# String_Shooter.net
KiCad netlist of a schematic drawn in EAGLE
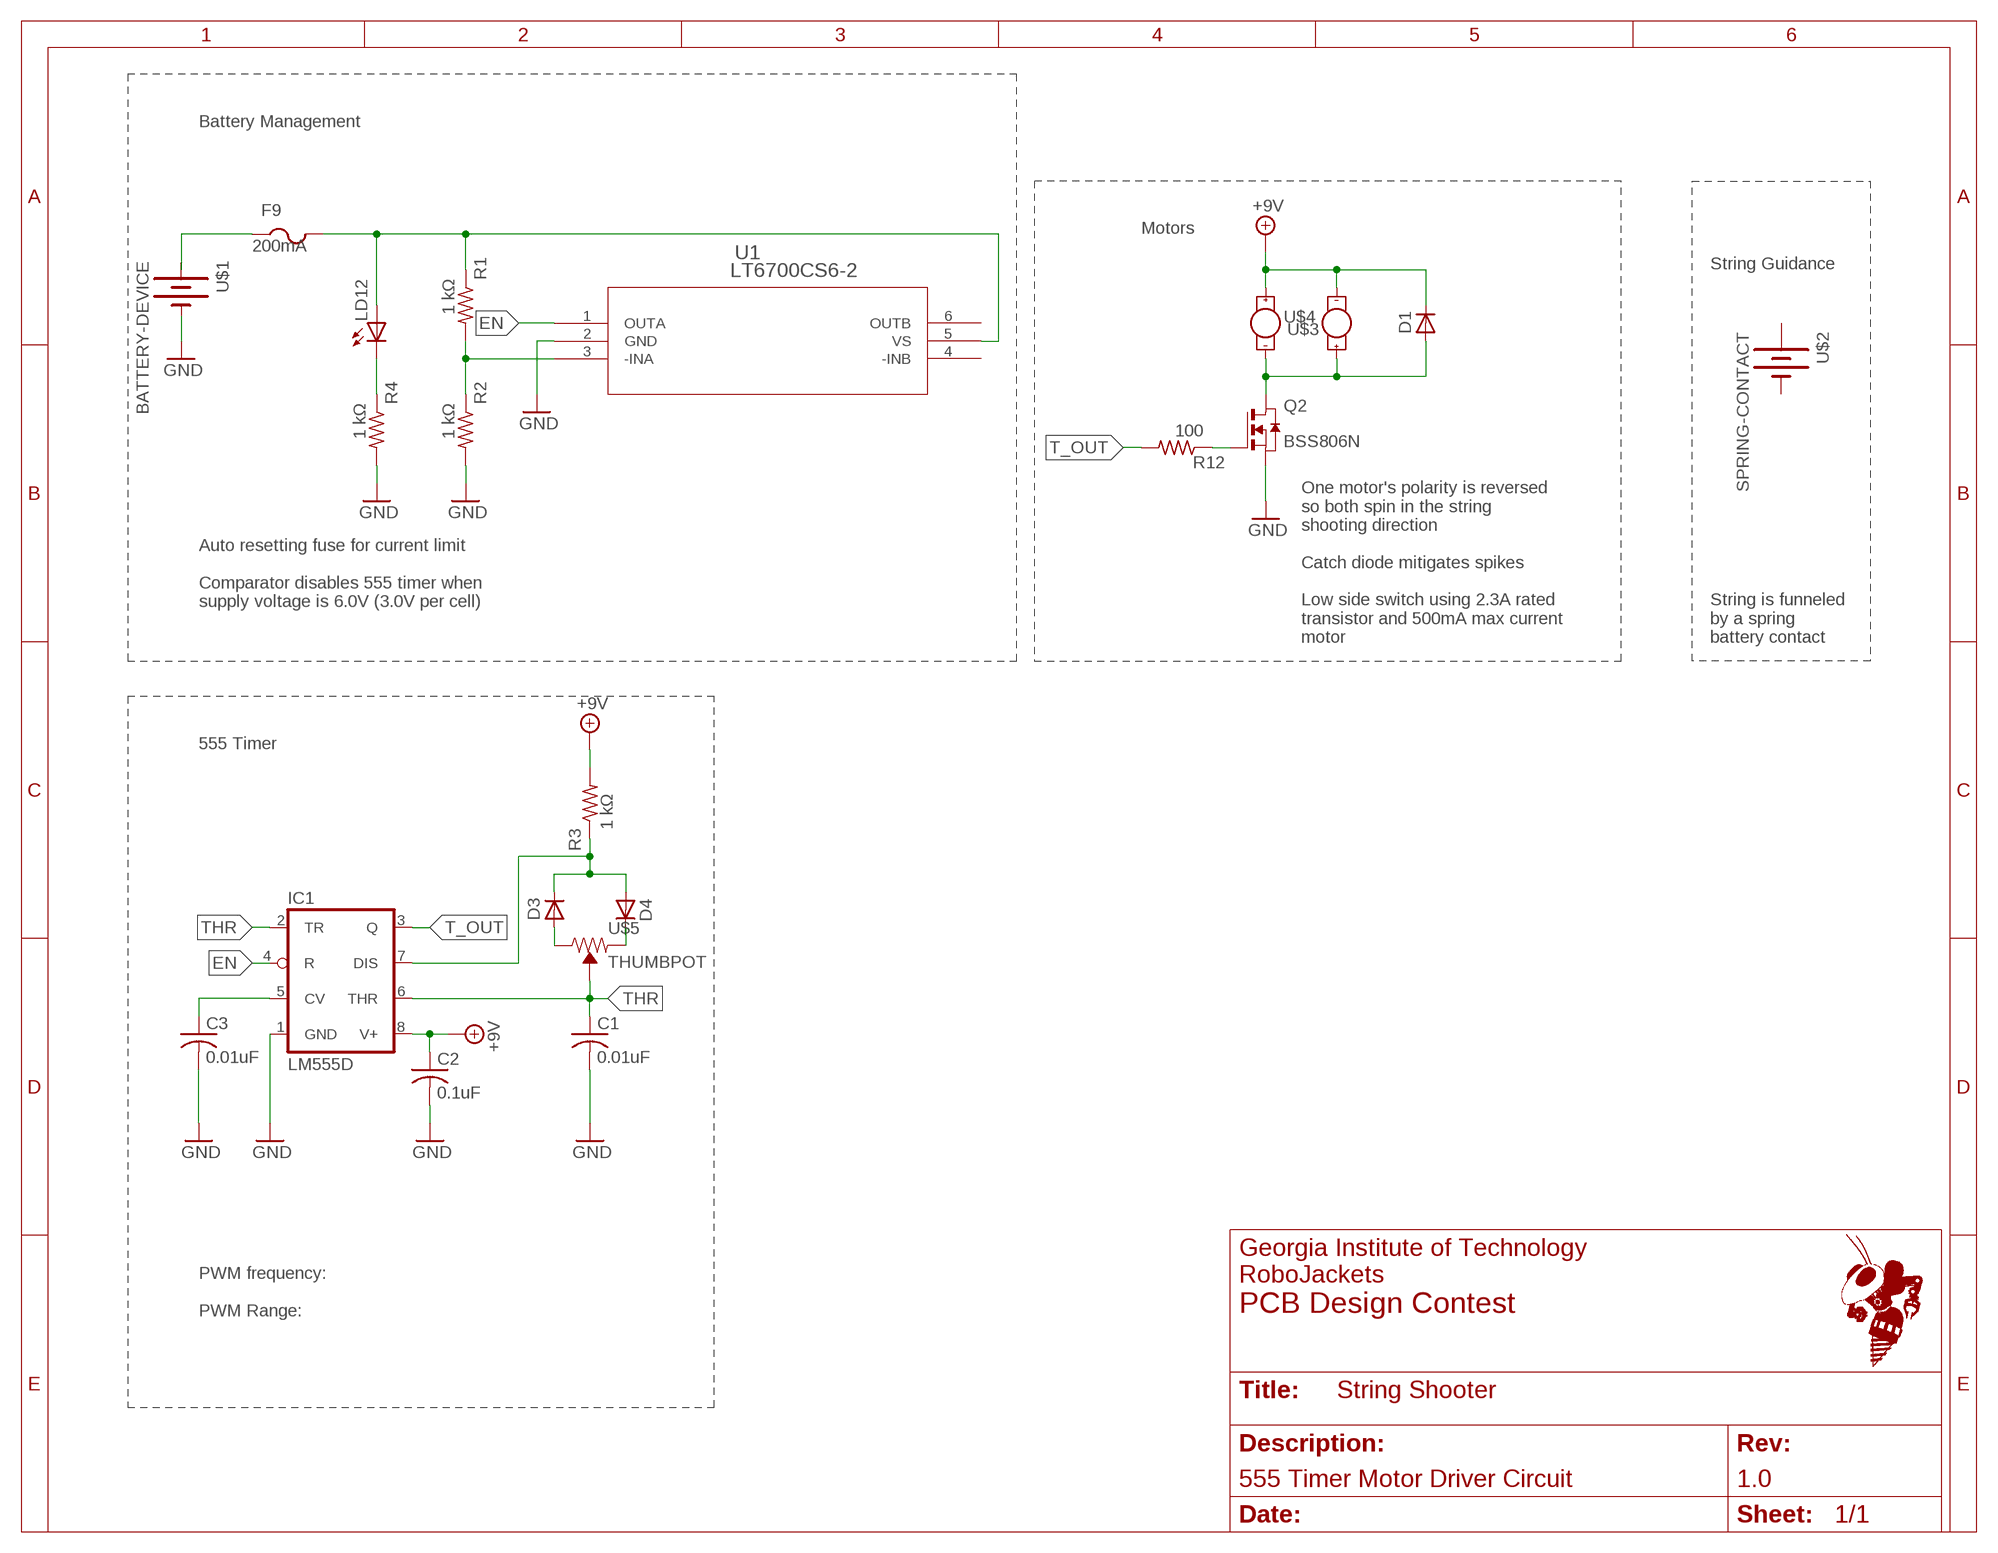
[diagram p0: schematic, sheet 1]

(export (version "E")
  (design (tool "Eeschema 10.0.6"))
  (components
    (comp (ref "C1")
      (value "0.01uF")
      (footprint "eagle-import:C0603")
      (libsource (lib "eagle-import") (part "C-USC0603"))
    )
    (comp (ref "C2")
      (value "0.1uF")
      (footprint "eagle-import:C0603")
      (libsource (lib "eagle-import") (part "C-USC0603"))
    )
    (comp (ref "C3")
      (value "0.01uF")
      (footprint "eagle-import:C0603")
      (libsource (lib "eagle-import") (part "C-USC0603"))
    )
    (comp (ref "D1")
      (value "DIODE-DO-214AC")
      (footprint "eagle-import:DO-214AC")
      (libsource (lib "eagle-import") (part "DIODE-DO-214AC"))
    )
    (comp (ref "D3")
      (value "DIODE-DO-214AC")
      (footprint "eagle-import:DO-214AC")
      (libsource (lib "eagle-import") (part "DIODE-DO-214AC"))
    )
    (comp (ref "D4")
      (value "DIODE-DO-214AC")
      (footprint "eagle-import:DO-214AC")
      (libsource (lib "eagle-import") (part "DIODE-DO-214AC"))
    )
    (comp (ref "F9")
      (value "200mA")
      (footprint "eagle-import:R1206")
      (libsource (lib "eagle-import") (part "PTCFUSE-1206"))
    )
    (comp (ref "IC1")
      (value "LM555D")
      (footprint "eagle-import:SO08")
      (libsource (lib "eagle-import") (part "555DLM"))
    )
    (comp (ref "LD12")
      (value "BLUE")
      (footprint "eagle-import:CHIP-LED0603")
      (libsource (lib "eagle-import") (part "LEDCHIP-LED0603"))
    )
    (comp (ref "Q2")
      (value "BSS806N")
      (footprint "eagle-import:SOT-23-3")
      (libsource (lib "eagle-import") (part "BSS806N"))
    )
    (comp (ref "R1")
      (value "1 kΩ")
      (footprint "eagle-import:R0603")
      (libsource (lib "eagle-import") (part "R-US_R0603"))
    )
    (comp (ref "R2")
      (value "1 kΩ")
      (footprint "eagle-import:R0603")
      (libsource (lib "eagle-import") (part "R-US_R0603"))
    )
    (comp (ref "R3")
      (value "1 kΩ")
      (footprint "eagle-import:R0603")
      (libsource (lib "eagle-import") (part "R-US_R0603"))
    )
    (comp (ref "R4")
      (value "1 kΩ")
      (footprint "eagle-import:R0603")
      (libsource (lib "eagle-import") (part "R-US_R0603"))
    )
    (comp (ref "R12")
      (value "100")
      (footprint "eagle-import:R0603")
      (libsource (lib "eagle-import") (part "R-US_R0603"))
    )
    (comp (ref "U$1")
      (value "BATTERY-DEVICE")
      (footprint "eagle-import:BATTERY-CASE")
      (libsource (lib "eagle-import") (part "BATTERY-DEVICE"))
    )
    (comp (ref "U$2")
      (value "SPRING-CONTACT")
      (footprint "eagle-import:SPRING-CONTACT")
      (libsource (lib "eagle-import") (part "SPRING-CONTACT"))
    )
    (comp (ref "U$3")
      (value "LITTLE-MOTOR")
      (footprint "eagle-import:DC_MOTOR")
      (libsource (lib "eagle-import") (part "LITTLE-MOTOR"))
    )
    (comp (ref "U$4")
      (value "LITTLE-MOTOR")
      (footprint "eagle-import:DC_MOTOR")
      (libsource (lib "eagle-import") (part "LITTLE-MOTOR"))
    )
    (comp (ref "U$5")
      (value "THUMBPOT")
      (footprint "eagle-import:THUMBWHEEL-POT")
      (libsource (lib "eagle-import") (part "THUMBPOT"))
    )
    (comp (ref "U1")
      (value "LT6700CS6-2")
      (footprint "eagle-import:TSOT-23_S6")
      (fields
        (field (name "DIGI-KEY_PART_NUMBER") "LT6700CS6-2#TRMPBFCT-ND")
        (field (name "MF") "Analog Devices / Linear Technology")
      )
      (libsource (lib "eagle-import") (part "LT6700CS6-2"))
    )
  )
  (nets
    (net (code "1") (name "+9V") (class "Default")
      (node (ref "C2") (pin "1") (pinfunction "1_1") (pintype "passive"))
      (node (ref "D1") (pin "C") (pinfunction "C_C") (pintype "passive"))
      (node (ref "IC1") (pin "8") (pinfunction "V+_8") (pintype "power_in"))
      (node (ref "R3") (pin "2") (pinfunction "2_2") (pintype "passive"))
    )
    (net (code "2") (name "EN") (class "Default")
      (node (ref "IC1") (pin "4") (pinfunction "R_4") (pintype "input"))
      (node (ref "U1") (pin "1") (pinfunction "OUTA_1") (pintype "output"))
    )
    (net (code "3") (name "GND") (class "Default")
      (node (ref "C1") (pin "2") (pinfunction "2_2") (pintype "passive"))
      (node (ref "C2") (pin "2") (pinfunction "2_2") (pintype "passive"))
      (node (ref "C3") (pin "2") (pinfunction "2_2") (pintype "passive"))
      (node (ref "IC1") (pin "1") (pinfunction "GND_1") (pintype "power_in"))
      (node (ref "Q2") (pin "2") (pinfunction "S_2") (pintype "passive"))
      (node (ref "R2") (pin "2") (pinfunction "2_2") (pintype "passive"))
      (node (ref "R4") (pin "2") (pinfunction "2_2") (pintype "passive"))
      (node (ref "U1") (pin "2") (pinfunction "GND_2") (pintype "power_in"))
    )
    (net (code "4") (name "Net-(IC1-CV)") (class "Default")
      (node (ref "C3") (pin "1") (pinfunction "1_1") (pintype "passive"))
      (node (ref "IC1") (pin "5") (pinfunction "CV_5") (pintype "input"))
    )
    (net (code "5") (name "Net-(IC1-DIS)") (class "Default")
      (node (ref "D3") (pin "C") (pinfunction "C_C") (pintype "passive"))
      (node (ref "D4") (pin "A") (pinfunction "A_A") (pintype "passive"))
      (node (ref "IC1") (pin "7") (pinfunction "DIS_7") (pintype "input"))
      (node (ref "R3") (pin "1") (pinfunction "1_1") (pintype "passive"))
    )
    (net (code "6") (name "Net-(LD12-PadC)") (class "Default")
      (node (ref "LD12") (pin "C") (pinfunction "C_C") (pintype "passive"))
      (node (ref "R4") (pin "1") (pinfunction "1_1") (pintype "passive"))
    )
    (net (code "7") (name "Net-(Q2-D)") (class "Default")
      (node (ref "D1") (pin "A") (pinfunction "A_A") (pintype "passive"))
      (node (ref "Q2") (pin "3") (pinfunction "D_3") (pintype "passive"))
    )
    (net (code "8") (name "Net-(Q2-G)") (class "Default")
      (node (ref "Q2") (pin "1") (pinfunction "G_1") (pintype "passive"))
      (node (ref "R12") (pin "1") (pinfunction "1_1") (pintype "passive"))
    )
    (net (code "9") (name "Net-(U$5-CCW)") (class "Default")
      (node (ref "D4") (pin "C") (pinfunction "C_C") (pintype "passive"))
      (node (ref "U$5") (pin "P$1") (pinfunction "CCW_P$1") (pintype "passive"))
    )
    (net (code "10") (name "Net-(U$5-CW)") (class "Default")
      (node (ref "D3") (pin "A") (pinfunction "A_A") (pintype "passive"))
      (node (ref "U$5") (pin "P$3") (pinfunction "CW_P$3") (pintype "passive"))
    )
    (net (code "11") (name "Net-(U1--INA)") (class "Default")
      (node (ref "R1") (pin "2") (pinfunction "2_2") (pintype "passive"))
      (node (ref "R2") (pin "1") (pinfunction "1_1") (pintype "passive"))
      (node (ref "U1") (pin "3") (pinfunction "-INA_3") (pintype "input"))
    )
    (net (code "12") (name "Net-(U1-VS)") (class "Default")
      (node (ref "F9") (pin "2") (pinfunction "2_2") (pintype "passive"))
      (node (ref "LD12") (pin "A") (pinfunction "A_A") (pintype "passive"))
      (node (ref "R1") (pin "1") (pinfunction "1_1") (pintype "passive"))
      (node (ref "U1") (pin "5") (pinfunction "VS_5") (pintype "power_in"))
    )
    (net (code "13") (name "THR") (class "Default")
      (node (ref "C1") (pin "1") (pinfunction "1_1") (pintype "passive"))
      (node (ref "IC1") (pin "2") (pinfunction "TR_2") (pintype "input"))
      (node (ref "IC1") (pin "6") (pinfunction "THR_6") (pintype "input"))
      (node (ref "U$5") (pin "P$2") (pinfunction "WIPER_P$2") (pintype "passive"))
    )
    (net (code "14") (name "T_OUT") (class "Default")
      (node (ref "IC1") (pin "3") (pinfunction "Q_3") (pintype "output"))
      (node (ref "R12") (pin "2") (pinfunction "2_2") (pintype "passive"))
    )
    (net (code "15") (name "unconnected-(F9-Pad1)") (class "Default")
      (node (ref "F9") (pin "1") (pinfunction "1_1") (pintype "passive"))
    )
    (net (code "16") (name "unconnected-(U1--INB-Pad4)") (class "Default")
      (node (ref "U1") (pin "4") (pinfunction "-INB_4") (pintype "input"))
    )
    (net (code "17") (name "unconnected-(U1-OUTB-Pad6)") (class "Default")
      (node (ref "U1") (pin "6") (pinfunction "OUTB_6") (pintype "output"))
    )
  )
)
